# MCU_144_POWER.net
KiCad netlist of a schematic drawn in Altium Designer
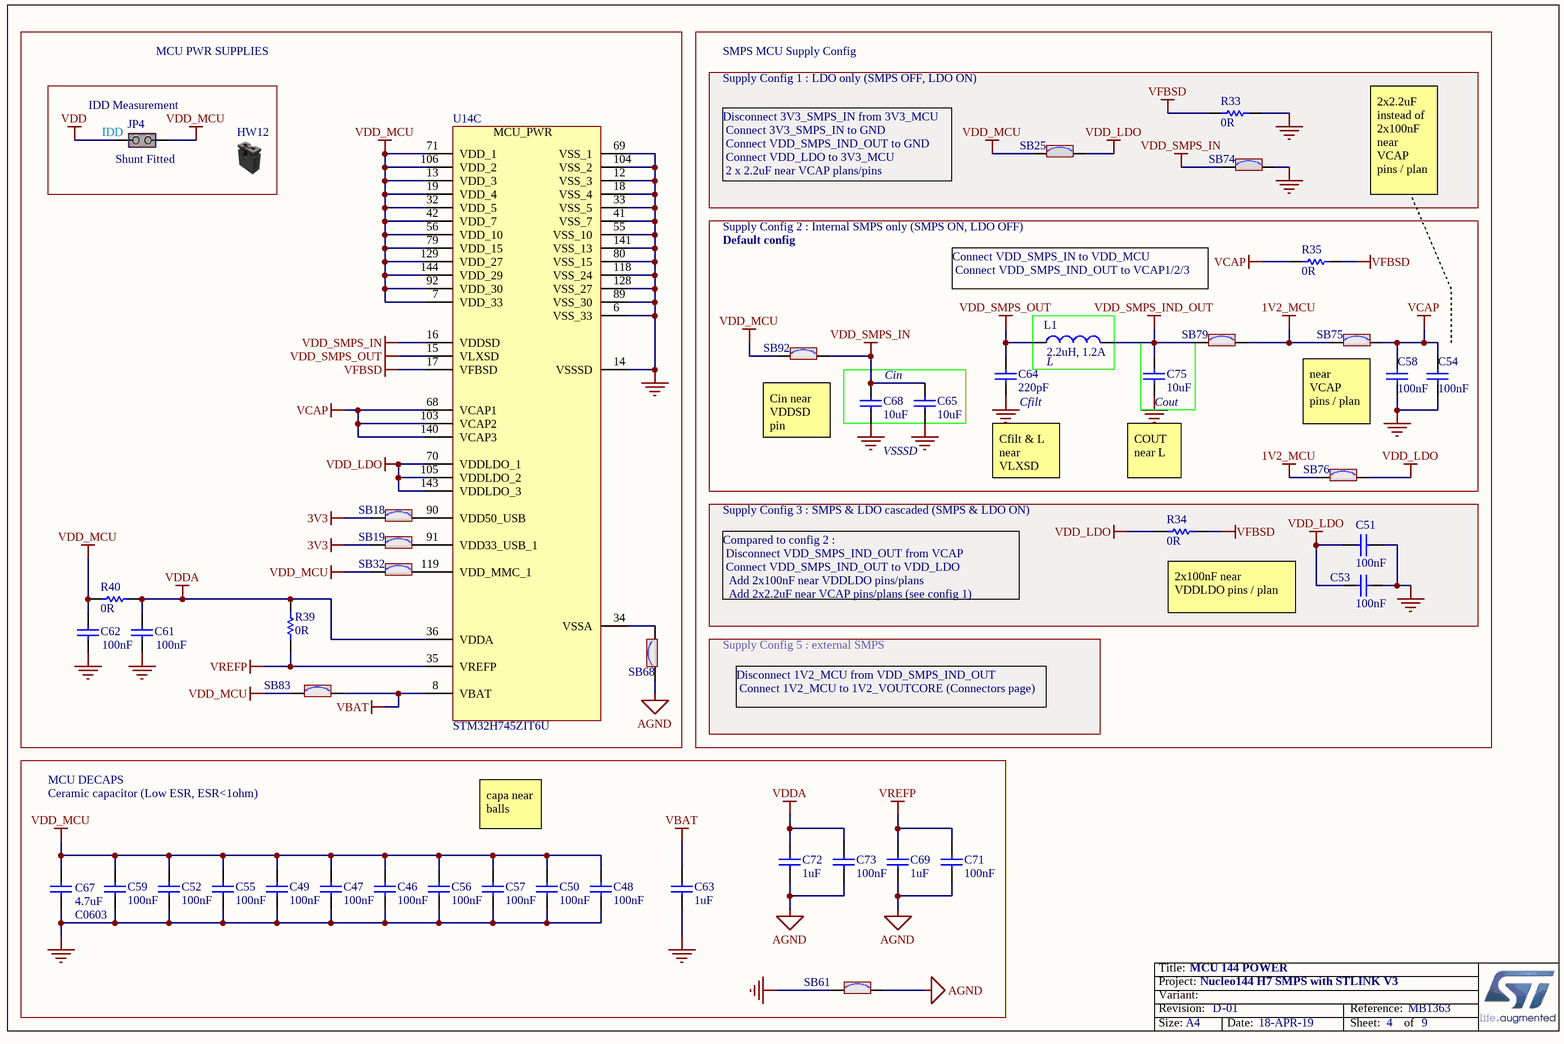
[diagram p0: MCU_144_POWER.SchDoc]

(export (version "E")
  (design (tool "Eeschema 10.0.6"))
  (components
    (comp (ref "C46")
      (value "100nF")
      (footprint "C0402")
      (description "Capacitor, MLCC, 100nF, 16V, X7R, 10%, 0402, T=0.5mm")
      (fields
        (field (name "INTERNAL_PART_NUMBER") "MCD-00006")
        (field (name "MANUFACTURER_PART_NUMBER") "CC0402KRX7R7BB104")
        (field (name "PROVIDED_BY") "SUBCO")
      )
      (libsource (lib "MCD_PARTS_database") (part "Capacitor"))
    )
    (comp (ref "C47")
      (value "100nF")
      (footprint "C0402")
      (description "Capacitor, MLCC, 100nF, 16V, X7R, 10%, 0402, T=0.5mm")
      (fields
        (field (name "INTERNAL_PART_NUMBER") "MCD-00006")
        (field (name "MANUFACTURER_PART_NUMBER") "CC0402KRX7R7BB104")
        (field (name "PROVIDED_BY") "SUBCO")
      )
      (libsource (lib "MCD_PARTS_database") (part "Capacitor"))
    )
    (comp (ref "C48")
      (value "100nF")
      (footprint "C0402")
      (description "Capacitor, MLCC, 100nF, 16V, X7R, 10%, 0402, T=0.5mm")
      (fields
        (field (name "INTERNAL_PART_NUMBER") "MCD-00006")
        (field (name "MANUFACTURER_PART_NUMBER") "CC0402KRX7R7BB104")
        (field (name "PROVIDED_BY") "SUBCO")
      )
      (libsource (lib "MCD_PARTS_database") (part "Capacitor"))
    )
    (comp (ref "C49")
      (value "100nF")
      (footprint "C0402")
      (description "Capacitor, MLCC, 100nF, 16V, X7R, 10%, 0402, T=0.5mm")
      (fields
        (field (name "INTERNAL_PART_NUMBER") "MCD-00006")
        (field (name "MANUFACTURER_PART_NUMBER") "CC0402KRX7R7BB104")
        (field (name "PROVIDED_BY") "SUBCO")
      )
      (libsource (lib "MCD_PARTS_database") (part "Capacitor"))
    )
    (comp (ref "C50")
      (value "100nF")
      (footprint "C0402")
      (description "Capacitor, MLCC, 100nF, 16V, X7R, 10%, 0402, T=0.5mm")
      (fields
        (field (name "INTERNAL_PART_NUMBER") "MCD-00006")
        (field (name "MANUFACTURER_PART_NUMBER") "CC0402KRX7R7BB104")
        (field (name "PROVIDED_BY") "SUBCO")
      )
      (libsource (lib "MCD_PARTS_database") (part "Capacitor"))
    )
    (comp (ref "C51")
      (value "100nF")
      (footprint "C0402")
      (description "Capacitor, MLCC, 100nF, 16V, X7R, 10%, 0402, T=0.5mm")
      (fields
        (field (name "INTERNAL_PART_NUMBER") "MCD-00006")
        (field (name "MANUFACTURER_PART_NUMBER") "CC0402KRX7R7BB104")
        (field (name "PROVIDED_BY") "SUBCO")
      )
      (libsource (lib "MCD_PARTS_database") (part "Capacitor"))
    )
    (comp (ref "C52")
      (value "100nF")
      (footprint "C0402")
      (description "Capacitor, MLCC, 100nF, 16V, X7R, 10%, 0402, T=0.5mm")
      (fields
        (field (name "INTERNAL_PART_NUMBER") "MCD-00006")
        (field (name "MANUFACTURER_PART_NUMBER") "CC0402KRX7R7BB104")
        (field (name "PROVIDED_BY") "SUBCO")
      )
      (libsource (lib "MCD_PARTS_database") (part "Capacitor"))
    )
    (comp (ref "C53")
      (value "100nF")
      (footprint "C0402")
      (description "Capacitor, MLCC, 100nF, 16V, X7R, 10%, 0402, T=0.5mm")
      (fields
        (field (name "INTERNAL_PART_NUMBER") "MCD-00006")
        (field (name "MANUFACTURER_PART_NUMBER") "CC0402KRX7R7BB104")
        (field (name "PROVIDED_BY") "SUBCO")
      )
      (libsource (lib "MCD_PARTS_database") (part "Capacitor"))
    )
    (comp (ref "C54")
      (value "100nF")
      (footprint "C0402")
      (description "Capacitor, MLCC, 100nF, 16V, X7R, 10%, 0402, T=0.5mm")
      (fields
        (field (name "INTERNAL_PART_NUMBER") "MCD-00006")
        (field (name "MANUFACTURER_PART_NUMBER") "CC0402KRX7R7BB104")
        (field (name "PROVIDED_BY") "SUBCO")
      )
      (libsource (lib "MCD_PARTS_database") (part "Capacitor"))
    )
    (comp (ref "C55")
      (value "100nF")
      (footprint "C0402")
      (description "Capacitor, MLCC, 100nF, 16V, X7R, 10%, 0402, T=0.5mm")
      (fields
        (field (name "INTERNAL_PART_NUMBER") "MCD-00006")
        (field (name "MANUFACTURER_PART_NUMBER") "CC0402KRX7R7BB104")
        (field (name "PROVIDED_BY") "SUBCO")
      )
      (libsource (lib "MCD_PARTS_database") (part "Capacitor"))
    )
    (comp (ref "C56")
      (value "100nF")
      (footprint "C0402")
      (description "Capacitor, MLCC, 100nF, 16V, X7R, 10%, 0402, T=0.5mm")
      (fields
        (field (name "INTERNAL_PART_NUMBER") "MCD-00006")
        (field (name "MANUFACTURER_PART_NUMBER") "CC0402KRX7R7BB104")
        (field (name "PROVIDED_BY") "SUBCO")
      )
      (libsource (lib "MCD_PARTS_database") (part "Capacitor"))
    )
    (comp (ref "C57")
      (value "100nF")
      (footprint "C0402")
      (description "Capacitor, MLCC, 100nF, 16V, X7R, 10%, 0402, T=0.5mm")
      (fields
        (field (name "INTERNAL_PART_NUMBER") "MCD-00006")
        (field (name "MANUFACTURER_PART_NUMBER") "CC0402KRX7R7BB104")
        (field (name "PROVIDED_BY") "SUBCO")
      )
      (libsource (lib "MCD_PARTS_database") (part "Capacitor"))
    )
    (comp (ref "C58")
      (value "100nF")
      (footprint "C0402")
      (description "Capacitor, MLCC, 100nF, 16V, X7R, 10%, 0402, T=0.5mm")
      (fields
        (field (name "INTERNAL_PART_NUMBER") "MCD-00006")
        (field (name "MANUFACTURER_PART_NUMBER") "CC0402KRX7R7BB104")
        (field (name "PROVIDED_BY") "SUBCO")
      )
      (libsource (lib "MCD_PARTS_database") (part "Capacitor"))
    )
    (comp (ref "C59")
      (value "100nF")
      (footprint "C0402")
      (description "Capacitor, MLCC, 100nF, 16V, X7R, 10%, 0402, T=0.5mm")
      (fields
        (field (name "INTERNAL_PART_NUMBER") "MCD-00006")
        (field (name "MANUFACTURER_PART_NUMBER") "CC0402KRX7R7BB104")
        (field (name "PROVIDED_BY") "SUBCO")
      )
      (libsource (lib "MCD_PARTS_database") (part "Capacitor"))
    )
    (comp (ref "C61")
      (value "100nF")
      (footprint "C0402")
      (description "Capacitor, MLCC, 100nF, 16V, X7R, 10%, 0402, T=0.5mm")
      (fields
        (field (name "INTERNAL_PART_NUMBER") "MCD-00006")
        (field (name "MANUFACTURER_PART_NUMBER") "CC0402KRX7R7BB104")
        (field (name "PROVIDED_BY") "SUBCO")
      )
      (libsource (lib "MCD_PARTS_database") (part "Capacitor"))
    )
    (comp (ref "C62")
      (value "100nF")
      (footprint "C0402")
      (description "Capacitor, MLCC, 100nF, 16V, X7R, 10%, 0402, T=0.5mm")
      (fields
        (field (name "INTERNAL_PART_NUMBER") "MCD-00006")
        (field (name "MANUFACTURER_PART_NUMBER") "CC0402KRX7R7BB104")
        (field (name "PROVIDED_BY") "SUBCO")
      )
      (libsource (lib "MCD_PARTS_database") (part "Capacitor"))
    )
    (comp (ref "C63")
      (value "1uF")
      (footprint "C0603")
      (description "Capacitor, MLCC, 1uF, 6V3, X5R, 10%, 0603, T=0,8mm")
      (fields
        (field (name "INTERNAL_PART_NUMBER") "MCD-00238")
        (field (name "MANUFACTURER_PART_NUMBER") "CC0603KRX5R5BB105")
        (field (name "PROVIDED_BY") "SUBCO")
      )
      (libsource (lib "MCD_PARTS_database") (part "Capacitor"))
    )
    (comp (ref "C64")
      (value "220pF")
      (footprint "C0402")
      (description "Capacitor, MLCC, 220pF, 50V, NPO, 5%, 0402, T=0,5mm")
      (fields
        (field (name "INTERNAL_PART_NUMBER") "MCD-01225")
        (field (name "MANUFACTURER_PART_NUMBER") "CC0402JRNPO9BN221")
        (field (name "PROVIDED_BY") "SUBCO")
      )
      (libsource (lib "MCD_PARTS_database") (part "Capacitor"))
    )
    (comp (ref "C65")
      (value "10uF")
      (footprint "C0402")
      (description "Capacitor, MLCC, 10uF, 6V3, X5R, 20%, 0402, T=0.5mm")
      (fields
        (field (name "INTERNAL_PART_NUMBER") "MCD-01716")
        (field (name "MANUFACTURER_PART_NUMBER") "CC0402MRX5R5BB106")
        (field (name "PROVIDED_BY") "SUBCO")
      )
      (libsource (lib "MCD_PARTS_database") (part "Capacitor"))
    )
    (comp (ref "C67")
      (value "4.7uF")
      (footprint "C0603")
      (description "Capacitor, MLCC, 4.7µF, 10V, X5R, 20%, 0603, T=0,8mm")
      (fields
        (field (name "INTERNAL_PART_NUMBER") "MCD-01121")
        (field (name "MANUFACTURER_PART_NUMBER") "GRM188R61A475ME15")
        (field (name "PACKAGE") "C0603")
        (field (name "PROVIDED_BY") "SUBCO")
      )
      (libsource (lib "MCD_PARTS_database") (part "Capacitor"))
    )
    (comp (ref "C68")
      (value "10uF")
      (footprint "C0402")
      (description "Capacitor, MLCC, 10uF, 6V3, X5R, 20%, 0402, T=0.5mm")
      (fields
        (field (name "INTERNAL_PART_NUMBER") "MCD-01716")
        (field (name "MANUFACTURER_PART_NUMBER") "CC0402MRX5R5BB106")
        (field (name "PROVIDED_BY") "SUBCO")
      )
      (libsource (lib "MCD_PARTS_database") (part "Capacitor"))
    )
    (comp (ref "C69")
      (value "1uF")
      (footprint "C0603")
      (description "Capacitor, MLCC, 1uF, 6V3, X5R, 10%, 0603, T=0,8mm")
      (fields
        (field (name "INTERNAL_PART_NUMBER") "MCD-00238")
        (field (name "MANUFACTURER_PART_NUMBER") "CC0603KRX5R5BB105")
        (field (name "PROVIDED_BY") "SUBCO")
      )
      (libsource (lib "MCD_PARTS_database") (part "Capacitor"))
    )
    (comp (ref "C71")
      (value "100nF")
      (footprint "C0402")
      (description "Capacitor, MLCC, 100nF, 16V, X7R, 10%, 0402, T=0.5mm")
      (fields
        (field (name "INTERNAL_PART_NUMBER") "MCD-00006")
        (field (name "MANUFACTURER_PART_NUMBER") "CC0402KRX7R7BB104")
        (field (name "PROVIDED_BY") "SUBCO")
      )
      (libsource (lib "MCD_PARTS_database") (part "Capacitor"))
    )
    (comp (ref "C72")
      (value "1uF")
      (footprint "C0603")
      (description "Capacitor, MLCC, 1uF, 6V3, X5R, 10%, 0603, T=0,8mm")
      (fields
        (field (name "INTERNAL_PART_NUMBER") "MCD-00238")
        (field (name "MANUFACTURER_PART_NUMBER") "CC0603KRX5R5BB105")
        (field (name "PROVIDED_BY") "SUBCO")
      )
      (libsource (lib "MCD_PARTS_database") (part "Capacitor"))
    )
    (comp (ref "C73")
      (value "100nF")
      (footprint "C0402")
      (description "Capacitor, MLCC, 100nF, 16V, X7R, 10%, 0402, T=0.5mm")
      (fields
        (field (name "INTERNAL_PART_NUMBER") "MCD-00006")
        (field (name "MANUFACTURER_PART_NUMBER") "CC0402KRX7R7BB104")
        (field (name "PROVIDED_BY") "SUBCO")
      )
      (libsource (lib "MCD_PARTS_database") (part "Capacitor"))
    )
    (comp (ref "C75")
      (value "10uF")
      (footprint "C0603")
      (description "Capacitor, MLCC, 10uF, 6V3, X5R, 20%, 0603, T=0,8mm")
      (fields
        (field (name "INTERNAL_PART_NUMBER") "MCD-01341")
        (field (name "MANUFACTURER_PART_NUMBER") "GRM188R60J106ME47D")
        (field (name "PROVIDED_BY") "SUBCO")
      )
      (libsource (lib "MCD_PARTS_database") (part "Capacitor"))
    )
    (comp (ref "HW12")
      (value "Shunt Black 2.54mm")
      (description "SHUNT 2.54mm BLACK")
      (fields
        (field (name "INTERNAL_PART_NUMBER") "MCD-00043")
        (field (name "MANUFACTURER_PART_NUMBER") "SNT-100-BK-G")
        (field (name "PROVIDED_BY") "SUBCO")
      )
      (libsource (lib "MCD_PARTS_database") (part "Shunt Black 2.54mm"))
    )
    (comp (ref "JP4")
      (value "Shunt Fitted")
      (footprint "CON_SAMTEC_TSW-102-07-G-S")
      (description "Header, 2x1, 2,54mm, VR, TH, Height 5.84mm/2.54mm - Shunt Fitted by default")
      (fields
        (field (name "INTERNAL_PART_NUMBER") "MCD-00683")
        (field (name "MANUFACTURER_PART_NUMBER") "TSW-102-07-x-S")
        (field (name "PROVIDED_BY") "SUBCO")
      )
      (libsource (lib "MCD_PARTS_database") (part "Jumper_Header 2x1 Fitted"))
    )
    (comp (ref "L1")
      (value "2.2uH, 1.2A")
      (footprint "L0805_H0P9")
      (description "Inductor, 2.2uH, 20%, Isat 1.2A, DCR 0.228Ohm, 0805")
      (fields
        (field (name "INTERNAL_PART_NUMBER") "MCD-01340")
        (field (name "MANUFACTURER_PART_NUMBER") "DFE201210U-2R2M=P2")
        (field (name "PROVIDED_BY") "SUBCO")
      )
      (libsource (lib "MCD_PARTS_database") (part "Inductor"))
    )
    (comp (ref "R33")
      (value "0R")
      (footprint "R0402")
      (description "Resistor,0R,0402,5%,1/16W")
      (fields
        (field (name "INTERNAL_PART_NUMBER") "MCD-00052")
        (field (name "MANUFACTURER_PART_NUMBER") "RC0402JR-070RL")
        (field (name "PROVIDED_BY") "SUBCO")
      )
      (libsource (lib "MCD_PARTS_database") (part "Resistor"))
    )
    (comp (ref "R34")
      (value "0R")
      (footprint "R0402")
      (description "Resistor,0R,0402,5%,1/16W")
      (fields
        (field (name "INTERNAL_PART_NUMBER") "MCD-00052")
        (field (name "MANUFACTURER_PART_NUMBER") "RC0402JR-070RL")
        (field (name "PROVIDED_BY") "SUBCO")
      )
      (libsource (lib "MCD_PARTS_database") (part "Resistor"))
    )
    (comp (ref "R35")
      (value "0R")
      (footprint "R0402")
      (description "Resistor,0R,0402,5%,1/16W")
      (fields
        (field (name "INTERNAL_PART_NUMBER") "MCD-00052")
        (field (name "MANUFACTURER_PART_NUMBER") "RC0402JR-070RL")
        (field (name "PROVIDED_BY") "SUBCO")
      )
      (libsource (lib "MCD_PARTS_database") (part "Resistor"))
    )
    (comp (ref "R39")
      (value "0R")
      (footprint "R0603")
      (description "Resistor,0R,0603,5%,1/10W")
      (fields
        (field (name "INTERNAL_PART_NUMBER") "MCD-00056")
        (field (name "MANUFACTURER_PART_NUMBER") "RC0603JR-070RL")
        (field (name "PROVIDED_BY") "SUBCO")
      )
      (libsource (lib "MCD_PARTS_database") (part "Resistor"))
    )
    (comp (ref "R40")
      (value "0R")
      (footprint "R0603")
      (description "Resistor,0R,0603,5%,1/10W")
      (fields
        (field (name "INTERNAL_PART_NUMBER") "MCD-00056")
        (field (name "MANUFACTURER_PART_NUMBER") "RC0603JR-070RL")
        (field (name "PROVIDED_BY") "SUBCO")
      )
      (libsource (lib "MCD_PARTS_database") (part "Resistor"))
    )
    (comp (ref "SB18")
      (value "SB_ON")
      (footprint "SOLDER-BRIDGE_R0603-0R")
      (description "Solder Bridge ON")
      (fields
        (field (name "INTERNAL_PART_NUMBER") "MCD-00071")
        (field (name "MANUFACTURER_PART_NUMBER") "RC0603JR-070RL")
        (field (name "PROVIDED_BY") "SUBCO")
      )
      (libsource (lib "MCD_PARTS_database") (part "SB_ON"))
    )
    (comp (ref "SB19")
      (value "SB_ON")
      (footprint "SOLDER-BRIDGE_R0603-0R")
      (description "Solder Bridge ON")
      (fields
        (field (name "INTERNAL_PART_NUMBER") "MCD-00071")
        (field (name "MANUFACTURER_PART_NUMBER") "RC0603JR-070RL")
        (field (name "PROVIDED_BY") "SUBCO")
      )
      (libsource (lib "MCD_PARTS_database") (part "SB_ON"))
    )
    (comp (ref "SB25")
      (value "SB_ON")
      (footprint "SOLDER-BRIDGE_R0603-0R")
      (description "Solder Bridge ON")
      (fields
        (field (name "INTERNAL_PART_NUMBER") "MCD-00071")
        (field (name "MANUFACTURER_PART_NUMBER") "RC0603JR-070RL")
        (field (name "PROVIDED_BY") "SUBCO")
      )
      (libsource (lib "MCD_PARTS_database") (part "SB_ON"))
    )
    (comp (ref "SB32")
      (value "SB_ON")
      (footprint "SOLDER-BRIDGE_R0603-0R")
      (description "Solder Bridge ON")
      (fields
        (field (name "INTERNAL_PART_NUMBER") "MCD-00071")
        (field (name "MANUFACTURER_PART_NUMBER") "RC0603JR-070RL")
        (field (name "PROVIDED_BY") "SUBCO")
      )
      (libsource (lib "MCD_PARTS_database") (part "SB_ON"))
    )
    (comp (ref "SB61")
      (value "SB_ON")
      (footprint "SOLDER-BRIDGE_R0603-0R")
      (description "Solder Bridge ON")
      (fields
        (field (name "INTERNAL_PART_NUMBER") "MCD-00071")
        (field (name "MANUFACTURER_PART_NUMBER") "RC0603JR-070RL")
        (field (name "PROVIDED_BY") "SUBCO")
      )
      (libsource (lib "") (part "SB_ON_2"))
    )
    (comp (ref "SB68")
      (value "SB_ON")
      (footprint "SOLDER-BRIDGE_R0603-0R")
      (description "Solder Bridge ON")
      (fields
        (field (name "INTERNAL_PART_NUMBER") "MCD-00071")
        (field (name "MANUFACTURER_PART_NUMBER") "RC0603JR-070RL")
        (field (name "PROVIDED_BY") "SUBCO")
      )
      (libsource (lib "") (part "SB_ON_1"))
    )
    (comp (ref "SB74")
      (value "SB_ON")
      (footprint "SOLDER-BRIDGE_R0603-0R")
      (description "Solder Bridge ON")
      (fields
        (field (name "INTERNAL_PART_NUMBER") "MCD-00071")
        (field (name "MANUFACTURER_PART_NUMBER") "RC0603JR-070RL")
        (field (name "PROVIDED_BY") "SUBCO")
      )
      (libsource (lib "MCD_PARTS_database") (part "SB_ON"))
    )
    (comp (ref "SB75")
      (value "SB_ON")
      (footprint "SOLDER-BRIDGE_R0603-0R")
      (description "Solder Bridge ON")
      (fields
        (field (name "INTERNAL_PART_NUMBER") "MCD-00071")
        (field (name "MANUFACTURER_PART_NUMBER") "RC0603JR-070RL")
        (field (name "PROVIDED_BY") "SUBCO")
      )
      (libsource (lib "MCD_PARTS_database") (part "SB_ON"))
    )
    (comp (ref "SB76")
      (value "SB_ON")
      (footprint "SOLDER-BRIDGE_R0603-0R")
      (description "Solder Bridge ON")
      (fields
        (field (name "INTERNAL_PART_NUMBER") "MCD-00071")
        (field (name "MANUFACTURER_PART_NUMBER") "RC0603JR-070RL")
        (field (name "PROVIDED_BY") "SUBCO")
      )
      (libsource (lib "MCD_PARTS_database") (part "SB_ON"))
    )
    (comp (ref "SB79")
      (value "SB_ON")
      (footprint "SOLDER-BRIDGE_R0603-0R")
      (description "Solder Bridge ON")
      (fields
        (field (name "INTERNAL_PART_NUMBER") "MCD-00071")
        (field (name "MANUFACTURER_PART_NUMBER") "RC0603JR-070RL")
        (field (name "PROVIDED_BY") "SUBCO")
      )
      (libsource (lib "MCD_PARTS_database") (part "SB_ON"))
    )
    (comp (ref "SB83")
      (value "SB_ON")
      (footprint "SOLDER-BRIDGE_R0603-0R")
      (description "Solder Bridge ON")
      (fields
        (field (name "INTERNAL_PART_NUMBER") "MCD-00071")
        (field (name "MANUFACTURER_PART_NUMBER") "RC0603JR-070RL")
        (field (name "PROVIDED_BY") "SUBCO")
      )
      (libsource (lib "") (part "SB_ON_2"))
    )
    (comp (ref "SB92")
      (value "SB_ON")
      (footprint "SOLDER-BRIDGE_R0603-0R")
      (description "Solder Bridge ON")
      (fields
        (field (name "INTERNAL_PART_NUMBER") "MCD-00071")
        (field (name "MANUFACTURER_PART_NUMBER") "RC0603JR-070RL")
        (field (name "PROVIDED_BY") "SUBCO")
      )
      (libsource (lib "MCD_PARTS_database") (part "SB_ON"))
    )
    (comp (ref "U14")
      (value "STM32H745ZIT6U")
      (footprint "ICC_LQFP144_20X20_P050_SOCKET_YAMAICHI_IC149-144-145-B5_NM")
      (description "STM32H745ZIT6U, LQFP144 package, 20x20, with socket footprint")
      (fields
        (field (name "INTERNAL_PART_NUMBER") "MCD-01401")
        (field (name "MANUFACTURER") "STMICROELECTRONICS")
        (field (name "PROVIDED_BY") "SUBCO with ST control")
      )
      (libsource (lib "MCD_PARTS_database") (part "STM32H7_LQFP144_SMPS"))
    )
  )
  (nets
    (net (code "1") (name "1V2_MCU") (class "Default")
      (node (ref "SB75") (pin "2") (pinfunction "2_2") (pintype "passive"))
      (node (ref "SB76") (pin "2") (pinfunction "2_2") (pintype "passive"))
      (node (ref "SB79") (pin "1") (pinfunction "1_1") (pintype "passive"))
    )
    (net (code "2") (name "3V3") (class "Default")
      (node (ref "SB18") (pin "2") (pinfunction "2_2") (pintype "passive"))
      (node (ref "SB19") (pin "2") (pinfunction "2_2") (pintype "passive"))
    )
    (net (code "3") (name "AGND") (class "Default")
      (node (ref "C69") (pin "2") (pinfunction "2_2") (pintype "passive"))
      (node (ref "C71") (pin "1") (pinfunction "1_1") (pintype "passive"))
      (node (ref "C72") (pin "2") (pinfunction "2_2") (pintype "passive"))
      (node (ref "C73") (pin "1") (pinfunction "1_1") (pintype "passive"))
      (node (ref "SB61") (pin "2") (pinfunction "2_2") (pintype "passive"))
      (node (ref "SB68") (pin "1") (pinfunction "1_1") (pintype "passive"))
    )
    (net (code "4") (name "GND") (class "Default")
      (node (ref "C46") (pin "1") (pinfunction "1_1") (pintype "passive"))
      (node (ref "C47") (pin "1") (pinfunction "1_1") (pintype "passive"))
      (node (ref "C48") (pin "1") (pinfunction "1_1") (pintype "passive"))
      (node (ref "C49") (pin "1") (pinfunction "1_1") (pintype "passive"))
      (node (ref "C50") (pin "1") (pinfunction "1_1") (pintype "passive"))
      (node (ref "C51") (pin "2") (pinfunction "2_2") (pintype "passive"))
      (node (ref "C52") (pin "1") (pinfunction "1_1") (pintype "passive"))
      (node (ref "C53") (pin "2") (pinfunction "2_2") (pintype "passive"))
      (node (ref "C54") (pin "1") (pinfunction "1_1") (pintype "passive"))
      (node (ref "C55") (pin "1") (pinfunction "1_1") (pintype "passive"))
      (node (ref "C56") (pin "1") (pinfunction "1_1") (pintype "passive"))
      (node (ref "C57") (pin "1") (pinfunction "1_1") (pintype "passive"))
      (node (ref "C58") (pin "1") (pinfunction "1_1") (pintype "passive"))
      (node (ref "C59") (pin "1") (pinfunction "1_1") (pintype "passive"))
      (node (ref "C61") (pin "2") (pinfunction "2_2") (pintype "passive"))
      (node (ref "C62") (pin "2") (pinfunction "2_2") (pintype "passive"))
      (node (ref "C63") (pin "1") (pinfunction "1_1") (pintype "passive"))
      (node (ref "C64") (pin "1") (pinfunction "1_1") (pintype "passive"))
      (node (ref "C65") (pin "1") (pinfunction "1_1") (pintype "passive"))
      (node (ref "C67") (pin "1") (pinfunction "1_1") (pintype "passive"))
      (node (ref "C68") (pin "1") (pinfunction "1_1") (pintype "passive"))
      (node (ref "C75") (pin "1") (pinfunction "1_1") (pintype "passive"))
      (node (ref "R33") (pin "2") (pinfunction "2_2") (pintype "passive"))
      (node (ref "SB61") (pin "1") (pinfunction "1_1") (pintype "passive"))
      (node (ref "SB74") (pin "1") (pinfunction "1_1") (pintype "passive"))
      (node (ref "U14") (pin "104") (pinfunction "VSS_2_104") (pintype "passive"))
      (node (ref "U14") (pin "118") (pinfunction "VSS_24_118") (pintype "passive"))
      (node (ref "U14") (pin "12") (pinfunction "VSS_3_12") (pintype "passive"))
      (node (ref "U14") (pin "128") (pinfunction "VSS_27_128") (pintype "passive"))
      (node (ref "U14") (pin "14") (pinfunction "VSSSD_14") (pintype "passive"))
      (node (ref "U14") (pin "141") (pinfunction "VSS_13_141") (pintype "passive"))
      (node (ref "U14") (pin "18") (pinfunction "VSS_4_18") (pintype "passive"))
      (node (ref "U14") (pin "33") (pinfunction "VSS_5_33") (pintype "passive"))
      (node (ref "U14") (pin "41") (pinfunction "VSS_7_41") (pintype "passive"))
      (node (ref "U14") (pin "55") (pinfunction "VSS_10_55") (pintype "passive"))
      (node (ref "U14") (pin "6") (pinfunction "VSS_33_6") (pintype "passive"))
      (node (ref "U14") (pin "69") (pinfunction "VSS_1_69") (pintype "passive"))
      (node (ref "U14") (pin "80") (pinfunction "VSS_15_80") (pintype "passive"))
      (node (ref "U14") (pin "89") (pinfunction "VSS_30_89") (pintype "passive"))
    )
    (net (code "5") (name "Net-(U14C-VDD33_USB_1)") (class "Default")
      (node (ref "SB19") (pin "1") (pinfunction "1_1") (pintype "passive"))
      (node (ref "U14") (pin "91") (pinfunction "VDD33_USB_1_91") (pintype "passive"))
    )
    (net (code "6") (name "Net-(U14C-VDD50_USB)") (class "Default")
      (node (ref "SB18") (pin "1") (pinfunction "1_1") (pintype "passive"))
      (node (ref "U14") (pin "90") (pinfunction "VDD50_USB_90") (pintype "passive"))
    )
    (net (code "7") (name "Net-(U14C-VDD_MMC_1)") (class "Default")
      (node (ref "SB32") (pin "1") (pinfunction "1_1") (pintype "passive"))
      (node (ref "U14") (pin "119") (pinfunction "VDD_MMC_1_119") (pintype "passive"))
    )
    (net (code "8") (name "Net-(U14C-VSSA)") (class "Default")
      (node (ref "SB68") (pin "2") (pinfunction "2_2") (pintype "passive"))
      (node (ref "U14") (pin "34") (pinfunction "VSSA_34") (pintype "passive"))
    )
    (net (code "9") (name "VBAT") (class "Default")
      (node (ref "C63") (pin "2") (pinfunction "2_2") (pintype "passive"))
      (node (ref "SB83") (pin "2") (pinfunction "2_2") (pintype "passive"))
      (node (ref "U14") (pin "8") (pinfunction "VBAT_8") (pintype "passive"))
    )
    (net (code "10") (name "VCAP") (class "Default")
      (node (ref "C54") (pin "2") (pinfunction "2_2") (pintype "passive"))
      (node (ref "C58") (pin "2") (pinfunction "2_2") (pintype "passive"))
      (node (ref "R35") (pin "1") (pinfunction "1_1") (pintype "passive"))
      (node (ref "SB75") (pin "1") (pinfunction "1_1") (pintype "passive"))
      (node (ref "U14") (pin "103") (pinfunction "VCAP2_103") (pintype "passive"))
      (node (ref "U14") (pin "140") (pinfunction "VCAP3_140") (pintype "passive"))
      (node (ref "U14") (pin "68") (pinfunction "VCAP1_68") (pintype "passive"))
    )
    (net (code "11") (name "VDD") (class "Default")
      (node (ref "JP4") (pin "1") (pinfunction "COMMON_1") (pintype "passive"))
    )
    (net (code "12") (name "VDDA") (class "Default")
      (node (ref "C61") (pin "1") (pinfunction "1_1") (pintype "passive"))
      (node (ref "C72") (pin "1") (pinfunction "1_1") (pintype "passive"))
      (node (ref "C73") (pin "2") (pinfunction "2_2") (pintype "passive"))
      (node (ref "R39") (pin "1") (pinfunction "1_1") (pintype "passive"))
      (node (ref "R40") (pin "2") (pinfunction "2_2") (pintype "passive"))
      (node (ref "U14") (pin "36") (pinfunction "VDDA_36") (pintype "passive"))
    )
    (net (code "13") (name "VDD_LDO") (class "Default")
      (node (ref "C51") (pin "1") (pinfunction "1_1") (pintype "passive"))
      (node (ref "C53") (pin "1") (pinfunction "1_1") (pintype "passive"))
      (node (ref "R34") (pin "1") (pinfunction "1_1") (pintype "passive"))
      (node (ref "SB25") (pin "1") (pinfunction "1_1") (pintype "passive"))
      (node (ref "SB76") (pin "1") (pinfunction "1_1") (pintype "passive"))
      (node (ref "U14") (pin "105") (pinfunction "VDDLDO_2_105") (pintype "passive"))
      (node (ref "U14") (pin "143") (pinfunction "VDDLDO_3_143") (pintype "passive"))
      (node (ref "U14") (pin "70") (pinfunction "VDDLDO_1_70") (pintype "passive"))
    )
    (net (code "14") (name "VDD_MCU") (class "Default")
      (node (ref "C46") (pin "2") (pinfunction "2_2") (pintype "passive"))
      (node (ref "C47") (pin "2") (pinfunction "2_2") (pintype "passive"))
      (node (ref "C48") (pin "2") (pinfunction "2_2") (pintype "passive"))
      (node (ref "C49") (pin "2") (pinfunction "2_2") (pintype "passive"))
      (node (ref "C50") (pin "2") (pinfunction "2_2") (pintype "passive"))
      (node (ref "C52") (pin "2") (pinfunction "2_2") (pintype "passive"))
      (node (ref "C55") (pin "2") (pinfunction "2_2") (pintype "passive"))
      (node (ref "C56") (pin "2") (pinfunction "2_2") (pintype "passive"))
      (node (ref "C57") (pin "2") (pinfunction "2_2") (pintype "passive"))
      (node (ref "C59") (pin "2") (pinfunction "2_2") (pintype "passive"))
      (node (ref "C62") (pin "1") (pinfunction "1_1") (pintype "passive"))
      (node (ref "C67") (pin "2") (pinfunction "2_2") (pintype "passive"))
      (node (ref "JP4") (pin "2") (pinfunction "NO_2") (pintype "passive"))
      (node (ref "R40") (pin "1") (pinfunction "1_1") (pintype "passive"))
      (node (ref "SB25") (pin "2") (pinfunction "2_2") (pintype "passive"))
      (node (ref "SB32") (pin "2") (pinfunction "2_2") (pintype "passive"))
      (node (ref "SB83") (pin "1") (pinfunction "1_1") (pintype "passive"))
      (node (ref "SB92") (pin "2") (pinfunction "2_2") (pintype "passive"))
      (node (ref "U14") (pin "106") (pinfunction "VDD_2_106") (pintype "passive"))
      (node (ref "U14") (pin "129") (pinfunction "VDD_27_129") (pintype "passive"))
      (node (ref "U14") (pin "13") (pinfunction "VDD_3_13") (pintype "passive"))
      (node (ref "U14") (pin "144") (pinfunction "VDD_29_144") (pintype "passive"))
      (node (ref "U14") (pin "19") (pinfunction "VDD_4_19") (pintype "passive"))
      (node (ref "U14") (pin "32") (pinfunction "VDD_5_32") (pintype "passive"))
      (node (ref "U14") (pin "42") (pinfunction "VDD_7_42") (pintype "passive"))
      (node (ref "U14") (pin "56") (pinfunction "VDD_10_56") (pintype "passive"))
      (node (ref "U14") (pin "7") (pinfunction "VDD_33_7") (pintype "passive"))
      (node (ref "U14") (pin "71") (pinfunction "VDD_1_71") (pintype "passive"))
      (node (ref "U14") (pin "79") (pinfunction "VDD_15_79") (pintype "passive"))
      (node (ref "U14") (pin "92") (pinfunction "VDD_30_92") (pintype "passive"))
    )
    (net (code "15") (name "VDD_SMPS_IN") (class "Default")
      (node (ref "C65") (pin "2") (pinfunction "2_2") (pintype "passive"))
      (node (ref "C68") (pin "2") (pinfunction "2_2") (pintype "passive"))
      (node (ref "SB74") (pin "2") (pinfunction "2_2") (pintype "passive"))
      (node (ref "SB92") (pin "1") (pinfunction "1_1") (pintype "passive"))
      (node (ref "U14") (pin "16") (pinfunction "VDDSD_16") (pintype "passive"))
    )
    (net (code "16") (name "VDD_SMPS_IND_OUT") (class "Default")
      (node (ref "C75") (pin "2") (pinfunction "2_2") (pintype "passive"))
      (node (ref "L1") (pin "2") (pinfunction "2_2") (pintype "passive"))
      (node (ref "SB79") (pin "2") (pinfunction "2_2") (pintype "passive"))
    )
    (net (code "17") (name "VDD_SMPS_OUT") (class "Default")
      (node (ref "C64") (pin "2") (pinfunction "2_2") (pintype "passive"))
      (node (ref "L1") (pin "1") (pinfunction "1_1") (pintype "passive"))
      (node (ref "U14") (pin "15") (pinfunction "VLXSD_15") (pintype "passive"))
    )
    (net (code "18") (name "VFBSD") (class "Default")
      (node (ref "R33") (pin "1") (pinfunction "1_1") (pintype "passive"))
      (node (ref "R34") (pin "2") (pinfunction "2_2") (pintype "passive"))
      (node (ref "R35") (pin "2") (pinfunction "2_2") (pintype "passive"))
      (node (ref "U14") (pin "17") (pinfunction "VFBSD_17") (pintype "passive"))
    )
    (net (code "19") (name "VREFP") (class "Default")
      (node (ref "C69") (pin "1") (pinfunction "1_1") (pintype "passive"))
      (node (ref "C71") (pin "2") (pinfunction "2_2") (pintype "passive"))
      (node (ref "R39") (pin "2") (pinfunction "2_2") (pintype "passive"))
      (node (ref "U14") (pin "35") (pinfunction "VREFP_35") (pintype "passive"))
    )
  )
)
